# CNC_shield_for_mkr1000_Sch.net
KiCad netlist of a schematic drawn in Altium Designer
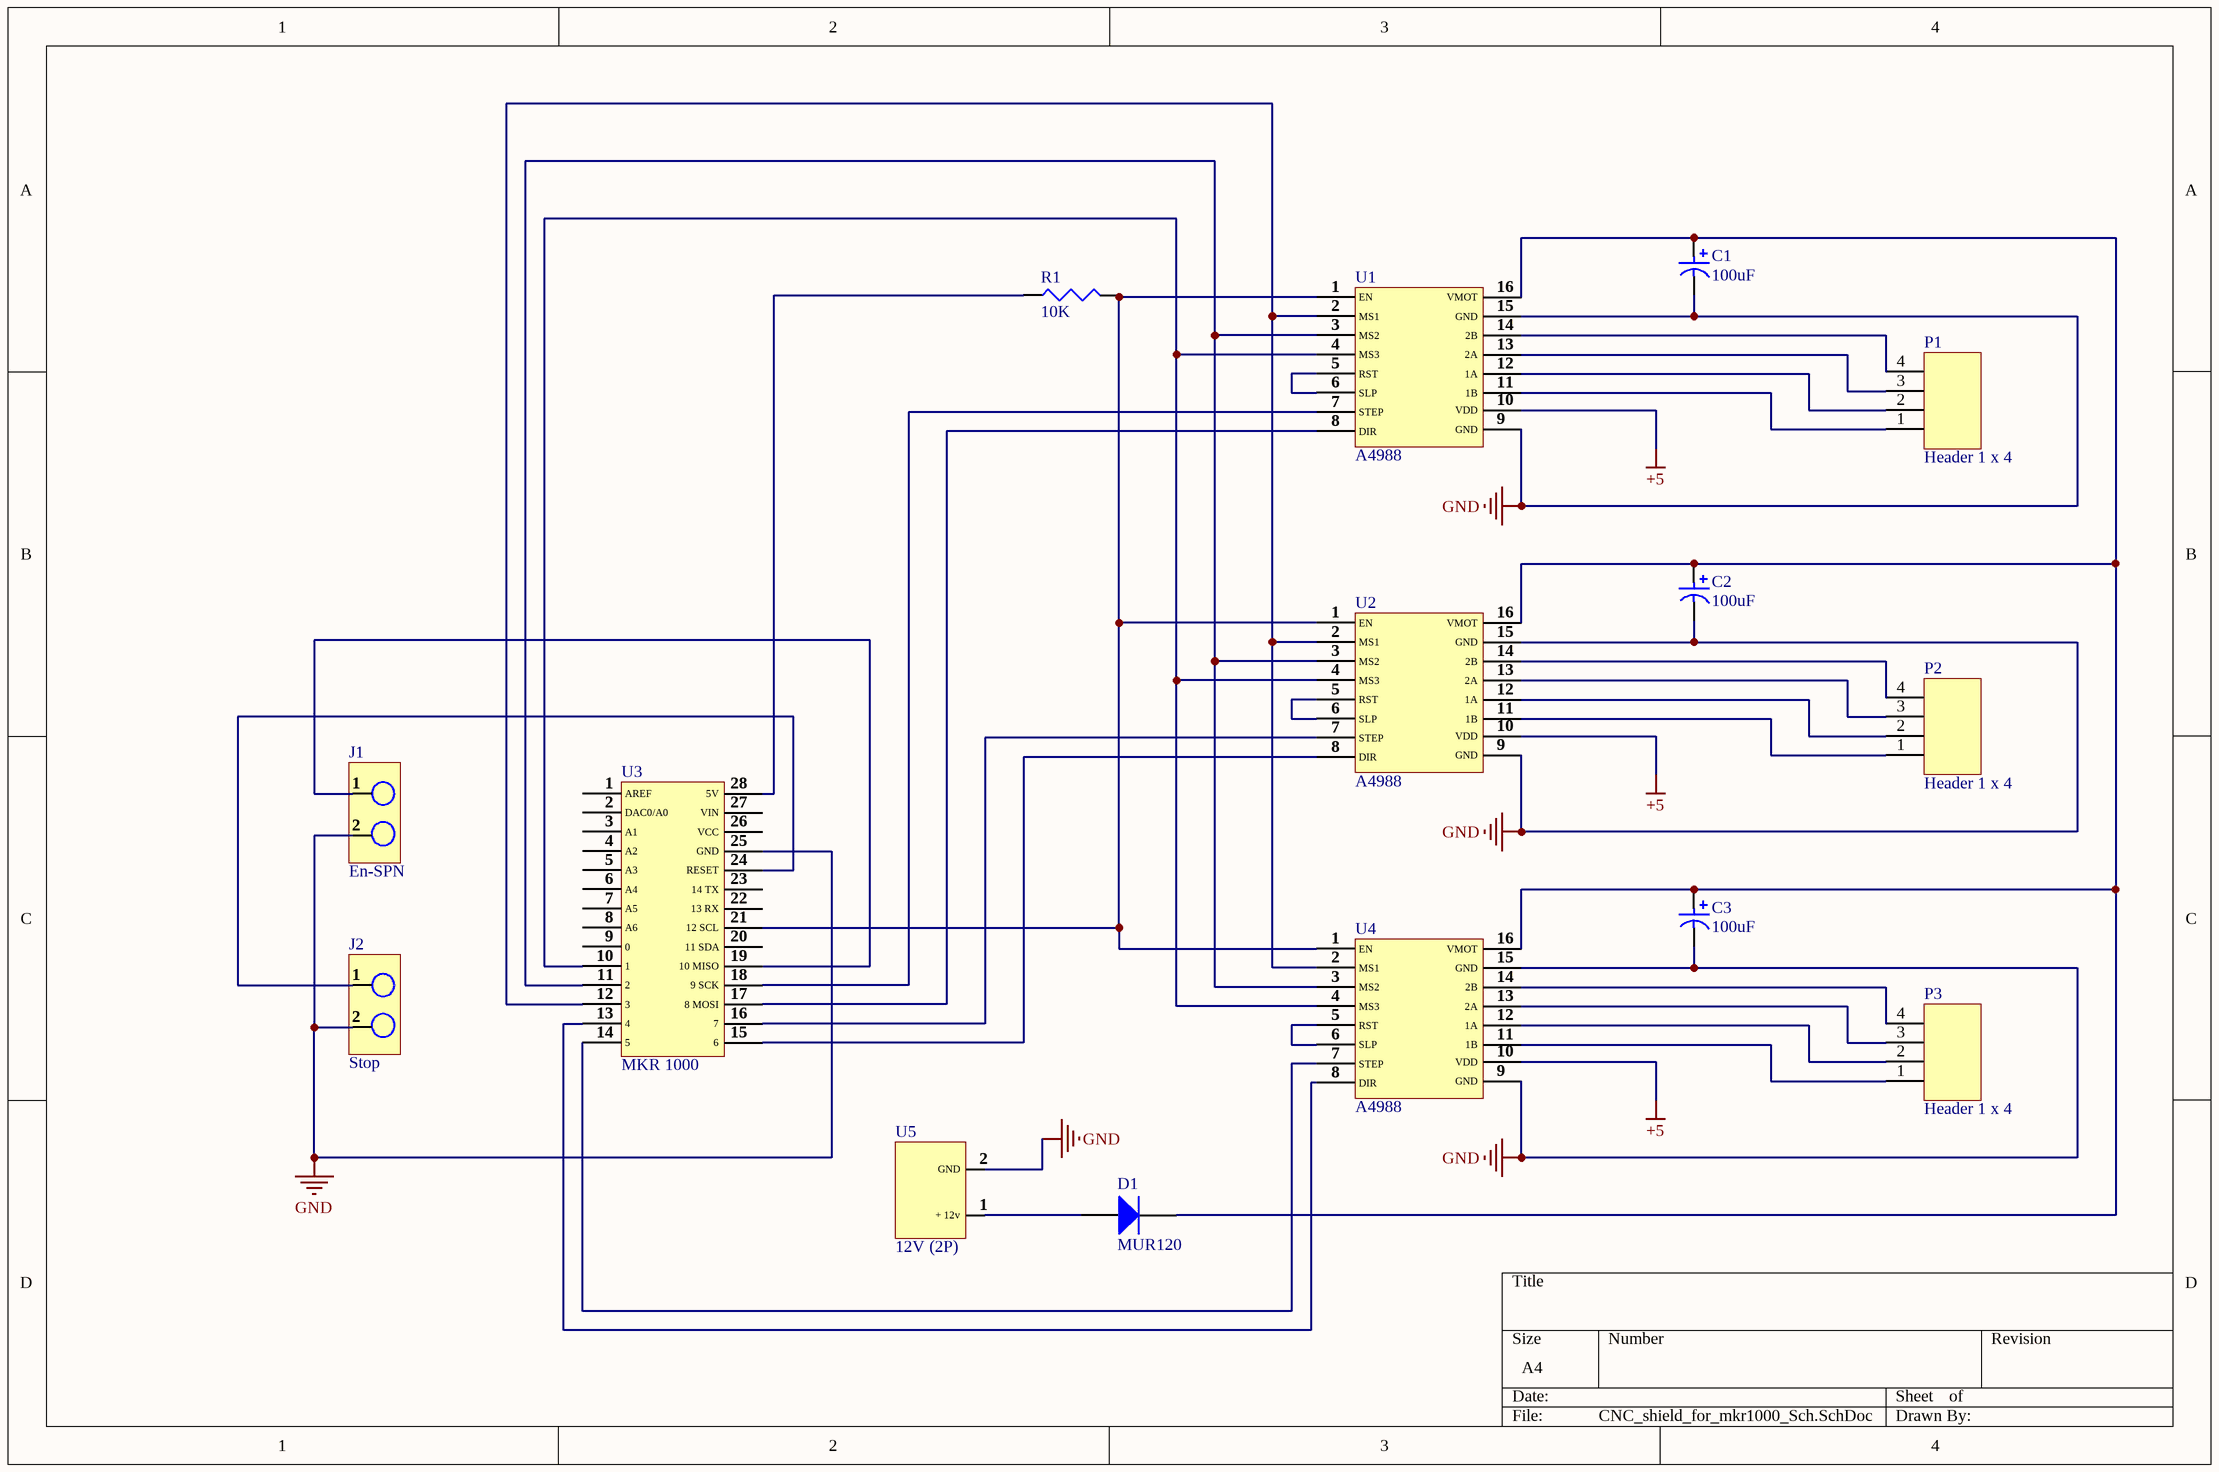
[diagram p0: CNC_shield_for_mkr1000_Sch.SchDoc]

(export (version "E")
  (design (tool "Eeschema 10.0.6"))
  (components
    (comp (ref "C1")
      (value "100uF")
      (footprint "CAP-D8.0XF3.5")
      (description "Polarized Capacitor (Surface Mount)")
      (fields (field (name "PUBLISHER") "Altium Limited"))
      (libsource (lib "altium-import") (part "root_3_Cap Pol3_"))
    )
    (comp (ref "C2")
      (value "100uF")
      (footprint "CAP-D8.0XF3.5")
      (description "Polarized Capacitor (Surface Mount)")
      (fields (field (name "PUBLISHER") "Altium Limited"))
      (libsource (lib "altium-import") (part "root_3_Cap Pol3_"))
    )
    (comp (ref "C3")
      (value "100uF")
      (footprint "CAP-D8.0XF3.5")
      (description "Polarized Capacitor (Surface Mount)")
      (fields (field (name "PUBLISHER") "Altium Limited"))
      (libsource (lib "altium-import") (part "root_3_Cap Pol3_"))
    )
    (comp (ref "D1")
      (value "MUR120")
      (footprint "DO-41")
      (description "Diode")
      (fields (field (name "PUBLISHER") "Altium Limited"))
      (libsource (lib "CNC_shield_for_mkr1000_SchLib") (part "MUR120"))
    )
    (comp (ref "J1")
      (value "En-SPN")
      (footprint "M1X2")
      (description "Jumper")
      (libsource (lib "altium-import") (part "root_0_En-SPN_"))
    )
    (comp (ref "J2")
      (value "Stop")
      (footprint "M1X2")
      (description "Jumper")
      (libsource (lib "altium-import") (part "root_0_Stop_"))
    )
    (comp (ref "P1")
      (value "Header 1 x 4")
      (footprint "HDR1X4")
      (description "Header, 4-Pin")
      (fields (field (name "PUBLISHER") "Altium Limited"))
      (libsource (lib "CNC_shield_for_mkr1000_SchLib") (part "Header 1 x 4"))
    )
    (comp (ref "P2")
      (value "Header 1 x 4")
      (footprint "HDR1X4")
      (description "Header, 4-Pin")
      (fields (field (name "PUBLISHER") "Altium Limited"))
      (libsource (lib "CNC_shield_for_mkr1000_SchLib") (part "Header 1 x 4"))
    )
    (comp (ref "P3")
      (value "Header 1 x 4")
      (footprint "HDR1X4")
      (description "Header, 4-Pin")
      (fields (field (name "PUBLISHER") "Altium Limited"))
      (libsource (lib "CNC_shield_for_mkr1000_SchLib") (part "Header 1 x 4"))
    )
    (comp (ref "R1")
      (value "10K")
      (footprint "AXIAL-0.4")
      (description "Resistor")
      (fields (field (name "PUBLISHER") "Altium Limited"))
      (libsource (lib "CNC_shield_for_mkr1000_SchLib") (part "10K"))
    )
    (comp (ref "U1")
      (value "A4988")
      (footprint "A4988 Stepper Motor Driver Carrier")
      (description "Motor Driver")
      (libsource (lib "altium-import") (part "root_0_A4988_"))
    )
    (comp (ref "U2")
      (value "A4988")
      (footprint "A4988 Stepper Motor Driver Carrier")
      (description "Motor Driver")
      (libsource (lib "altium-import") (part "root_0_A4988_"))
    )
    (comp (ref "U3")
      (value "MKR 1000")
      (footprint "MKR 1000")
      (description "Arduino wifi")
      (libsource (lib "altium-import") (part "root_0_Arduino MKR 1000_"))
    )
    (comp (ref "U4")
      (value "A4988")
      (footprint "A4988 Stepper Motor Driver Carrier")
      (description "Motor Driver")
      (libsource (lib "altium-import") (part "root_0_A4988_"))
    )
    (comp (ref "U5")
      (value "12V (2P)")
      (footprint "BORNERA 2 PINES")
      (description "IC")
      (libsource (lib "altium-import") (part "root_0_12V (2P)_"))
    )
  )
  (nets
    (net (code "1") (name "+5") (class "Default")
      (node (ref "U1") (pin "10") (pinfunction "VDD_10") (pintype "passive"))
      (node (ref "U2") (pin "10") (pinfunction "VDD_10") (pintype "passive"))
      (node (ref "U4") (pin "10") (pinfunction "VDD_10") (pintype "passive"))
    )
    (net (code "2") (name "GND") (class "Default")
      (node (ref "C1") (pin "2") (pinfunction "2_2") (pintype "passive"))
      (node (ref "C2") (pin "2") (pinfunction "2_2") (pintype "passive"))
      (node (ref "C3") (pin "2") (pinfunction "2_2") (pintype "passive"))
      (node (ref "J1") (pin "2") (pinfunction "2_2") (pintype "passive"))
      (node (ref "J2") (pin "2") (pinfunction "2_2") (pintype "passive"))
      (node (ref "U1") (pin "15") (pinfunction "GND_15") (pintype "passive"))
      (node (ref "U1") (pin "9") (pinfunction "GND_9") (pintype "passive"))
      (node (ref "U2") (pin "15") (pinfunction "GND_15") (pintype "passive"))
      (node (ref "U2") (pin "9") (pinfunction "GND_9") (pintype "passive"))
      (node (ref "U3") (pin "25") (pinfunction "GND_25") (pintype "passive"))
      (node (ref "U4") (pin "15") (pinfunction "GND_15") (pintype "passive"))
      (node (ref "U4") (pin "9") (pinfunction "GND_9") (pintype "passive"))
      (node (ref "U5") (pin "2") (pinfunction "GND_2") (pintype "passive"))
    )
    (net (code "3") (name "Net-(D1-A)") (class "Default")
      (node (ref "D1") (pin "1") (pinfunction "A_1") (pintype "passive"))
      (node (ref "U5") (pin "1") (pinfunction "+_12v_1") (pintype "passive"))
    )
    (net (code "4") (name "Net-(D1-K)") (class "Default")
      (node (ref "C1") (pin "1") (pinfunction "1_1") (pintype "passive"))
      (node (ref "C2") (pin "1") (pinfunction "1_1") (pintype "passive"))
      (node (ref "C3") (pin "1") (pinfunction "1_1") (pintype "passive"))
      (node (ref "D1") (pin "2") (pinfunction "K_2") (pintype "passive"))
      (node (ref "U1") (pin "16") (pinfunction "VMOT_16") (pintype "passive"))
      (node (ref "U2") (pin "16") (pinfunction "VMOT_16") (pintype "passive"))
      (node (ref "U4") (pin "16") (pinfunction "VMOT_16") (pintype "passive"))
    )
    (net (code "5") (name "Net-(J1-EN)") (class "Default")
      (node (ref "J1") (pin "1") (pinfunction "EN_1") (pintype "passive"))
      (node (ref "U3") (pin "19") (pinfunction "10_MISO_19") (pintype "passive"))
    )
    (net (code "6") (name "Net-(J2-EN)") (class "Default")
      (node (ref "J2") (pin "1") (pinfunction "EN_1") (pintype "passive"))
      (node (ref "U3") (pin "24") (pinfunction "RESET_24") (pintype "passive"))
    )
    (net (code "7") (name "Net-(P1-1)") (class "Default")
      (node (ref "P1") (pin "4") (pinfunction "1_4") (pintype "passive"))
      (node (ref "U1") (pin "14") (pinfunction "2B_14") (pintype "passive"))
    )
    (net (code "8") (name "Net-(P1-4)") (class "Default")
      (node (ref "P1") (pin "1") (pinfunction "4_1") (pintype "passive"))
      (node (ref "U1") (pin "11") (pinfunction "1B_11") (pintype "passive"))
    )
    (net (code "9") (name "Net-(P2-1)") (class "Default")
      (node (ref "P2") (pin "4") (pinfunction "1_4") (pintype "passive"))
      (node (ref "U2") (pin "14") (pinfunction "2B_14") (pintype "passive"))
    )
    (net (code "10") (name "Net-(P2-4)") (class "Default")
      (node (ref "P2") (pin "1") (pinfunction "4_1") (pintype "passive"))
      (node (ref "U2") (pin "11") (pinfunction "1B_11") (pintype "passive"))
    )
    (net (code "11") (name "Net-(P3-1)") (class "Default")
      (node (ref "P3") (pin "4") (pinfunction "1_4") (pintype "passive"))
      (node (ref "U4") (pin "14") (pinfunction "2B_14") (pintype "passive"))
    )
    (net (code "12") (name "Net-(P3-4)") (class "Default")
      (node (ref "P3") (pin "1") (pinfunction "4_1") (pintype "passive"))
      (node (ref "U4") (pin "11") (pinfunction "1B_11") (pintype "passive"))
    )
    (net (code "13") (name "Net-(U1-1A)") (class "Default")
      (node (ref "P1") (pin "2") (pinfunction "2_2") (pintype "passive"))
      (node (ref "U1") (pin "12") (pinfunction "1A_12") (pintype "passive"))
    )
    (net (code "14") (name "Net-(U1-2A)") (class "Default")
      (node (ref "P1") (pin "3") (pinfunction "2_3") (pintype "passive"))
      (node (ref "U1") (pin "13") (pinfunction "2A_13") (pintype "passive"))
    )
    (net (code "15") (name "Net-(U1-DIR)") (class "Default")
      (node (ref "U1") (pin "8") (pinfunction "DIR_8") (pintype "passive"))
      (node (ref "U3") (pin "17") (pinfunction "8_MOSI_17") (pintype "passive"))
    )
    (net (code "16") (name "Net-(U1-EN)") (class "Default")
      (node (ref "R1") (pin "2") (pinfunction "2_2") (pintype "passive"))
      (node (ref "U1") (pin "1") (pinfunction "EN_1") (pintype "passive"))
      (node (ref "U2") (pin "1") (pinfunction "EN_1") (pintype "passive"))
      (node (ref "U3") (pin "21") (pinfunction "12_SCL_21") (pintype "passive"))
      (node (ref "U4") (pin "1") (pinfunction "EN_1") (pintype "passive"))
    )
    (net (code "17") (name "Net-(U1-MS1)") (class "Default")
      (node (ref "U1") (pin "2") (pinfunction "MS1_2") (pintype "passive"))
      (node (ref "U2") (pin "2") (pinfunction "MS1_2") (pintype "passive"))
      (node (ref "U3") (pin "12") (pinfunction "3_12") (pintype "passive"))
      (node (ref "U4") (pin "2") (pinfunction "MS1_2") (pintype "passive"))
    )
    (net (code "18") (name "Net-(U1-MS2)") (class "Default")
      (node (ref "U1") (pin "3") (pinfunction "MS2_3") (pintype "passive"))
      (node (ref "U2") (pin "3") (pinfunction "MS2_3") (pintype "passive"))
      (node (ref "U3") (pin "11") (pinfunction "2_11") (pintype "passive"))
      (node (ref "U4") (pin "3") (pinfunction "MS2_3") (pintype "passive"))
    )
    (net (code "19") (name "Net-(U1-MS3)") (class "Default")
      (node (ref "U1") (pin "4") (pinfunction "MS3_4") (pintype "passive"))
      (node (ref "U2") (pin "4") (pinfunction "MS3_4") (pintype "passive"))
      (node (ref "U3") (pin "10") (pinfunction "1_10") (pintype "passive"))
      (node (ref "U4") (pin "4") (pinfunction "MS3_4") (pintype "passive"))
    )
    (net (code "20") (name "Net-(U1-RST)") (class "Default")
      (node (ref "U1") (pin "5") (pinfunction "RST_5") (pintype "passive"))
      (node (ref "U1") (pin "6") (pinfunction "SLP_6") (pintype "passive"))
    )
    (net (code "21") (name "Net-(U1-STEP)") (class "Default")
      (node (ref "U1") (pin "7") (pinfunction "STEP_7") (pintype "passive"))
      (node (ref "U3") (pin "18") (pinfunction "9_SCK_18") (pintype "passive"))
    )
    (net (code "22") (name "Net-(U2-1A)") (class "Default")
      (node (ref "P2") (pin "2") (pinfunction "2_2") (pintype "passive"))
      (node (ref "U2") (pin "12") (pinfunction "1A_12") (pintype "passive"))
    )
    (net (code "23") (name "Net-(U2-2A)") (class "Default")
      (node (ref "P2") (pin "3") (pinfunction "2_3") (pintype "passive"))
      (node (ref "U2") (pin "13") (pinfunction "2A_13") (pintype "passive"))
    )
    (net (code "24") (name "Net-(U2-DIR)") (class "Default")
      (node (ref "U2") (pin "8") (pinfunction "DIR_8") (pintype "passive"))
      (node (ref "U3") (pin "15") (pinfunction "6_15") (pintype "passive"))
    )
    (net (code "25") (name "Net-(U2-RST)") (class "Default")
      (node (ref "U2") (pin "5") (pinfunction "RST_5") (pintype "passive"))
      (node (ref "U2") (pin "6") (pinfunction "SLP_6") (pintype "passive"))
    )
    (net (code "26") (name "Net-(U2-STEP)") (class "Default")
      (node (ref "U2") (pin "7") (pinfunction "STEP_7") (pintype "passive"))
      (node (ref "U3") (pin "16") (pinfunction "7_16") (pintype "passive"))
    )
    (net (code "27") (name "Net-(U3-4)") (class "Default")
      (node (ref "U3") (pin "13") (pinfunction "4_13") (pintype "passive"))
      (node (ref "U4") (pin "8") (pinfunction "DIR_8") (pintype "passive"))
    )
    (net (code "28") (name "Net-(U3-5)") (class "Default")
      (node (ref "U3") (pin "14") (pinfunction "5_14") (pintype "passive"))
      (node (ref "U4") (pin "7") (pinfunction "STEP_7") (pintype "passive"))
    )
    (net (code "29") (name "Net-(U3-5V)") (class "Default")
      (node (ref "R1") (pin "1") (pinfunction "1_1") (pintype "passive"))
      (node (ref "U3") (pin "28") (pinfunction "5V_28") (pintype "passive"))
    )
    (net (code "30") (name "Net-(U4-1A)") (class "Default")
      (node (ref "P3") (pin "2") (pinfunction "2_2") (pintype "passive"))
      (node (ref "U4") (pin "12") (pinfunction "1A_12") (pintype "passive"))
    )
    (net (code "31") (name "Net-(U4-2A)") (class "Default")
      (node (ref "P3") (pin "3") (pinfunction "2_3") (pintype "passive"))
      (node (ref "U4") (pin "13") (pinfunction "2A_13") (pintype "passive"))
    )
    (net (code "32") (name "Net-(U4-RST)") (class "Default")
      (node (ref "U4") (pin "5") (pinfunction "RST_5") (pintype "passive"))
      (node (ref "U4") (pin "6") (pinfunction "SLP_6") (pintype "passive"))
    )
    (net (code "33") (name "unconnected-(U3-0-Pad9)") (class "Default")
      (node (ref "U3") (pin "9") (pinfunction "0_9") (pintype "passive"))
    )
    (net (code "34") (name "unconnected-(U3-11_SDA-Pad20)") (class "Default")
      (node (ref "U3") (pin "20") (pinfunction "11_SDA_20") (pintype "passive"))
    )
    (net (code "35") (name "unconnected-(U3-13_RX-Pad22)") (class "Default")
      (node (ref "U3") (pin "22") (pinfunction "13_RX_22") (pintype "passive"))
    )
    (net (code "36") (name "unconnected-(U3-14_TX-Pad23)") (class "Default")
      (node (ref "U3") (pin "23") (pinfunction "14_TX_23") (pintype "passive"))
    )
    (net (code "37") (name "unconnected-(U3-A1-Pad3)") (class "Default")
      (node (ref "U3") (pin "3") (pinfunction "A1_3") (pintype "passive"))
    )
    (net (code "38") (name "unconnected-(U3-A2-Pad4)") (class "Default")
      (node (ref "U3") (pin "4") (pinfunction "A2_4") (pintype "passive"))
    )
    (net (code "39") (name "unconnected-(U3-A3-Pad5)") (class "Default")
      (node (ref "U3") (pin "5") (pinfunction "A3_5") (pintype "passive"))
    )
    (net (code "40") (name "unconnected-(U3-A4-Pad6)") (class "Default")
      (node (ref "U3") (pin "6") (pinfunction "A4_6") (pintype "passive"))
    )
    (net (code "41") (name "unconnected-(U3-A5-Pad7)") (class "Default")
      (node (ref "U3") (pin "7") (pinfunction "A5_7") (pintype "passive"))
    )
    (net (code "42") (name "unconnected-(U3-A6-Pad8)") (class "Default")
      (node (ref "U3") (pin "8") (pinfunction "A6_8") (pintype "passive"))
    )
    (net (code "43") (name "unconnected-(U3-AREF-Pad1)") (class "Default")
      (node (ref "U3") (pin "1") (pinfunction "AREF_1") (pintype "passive"))
    )
    (net (code "44") (name "unconnected-(U3-DAC0{slash}A0-Pad2)") (class "Default")
      (node (ref "U3") (pin "2") (pinfunction "DAC0/A0_2") (pintype "passive"))
    )
    (net (code "45") (name "unconnected-(U3-VCC-Pad26)") (class "Default")
      (node (ref "U3") (pin "26") (pinfunction "VCC_26") (pintype "passive"))
    )
    (net (code "46") (name "unconnected-(U3-VIN-Pad27)") (class "Default")
      (node (ref "U3") (pin "27") (pinfunction "VIN_27") (pintype "passive"))
    )
  )
)
